# 1u_panel_v1_1.net
KiCad netlist of a schematic drawn in EAGLE
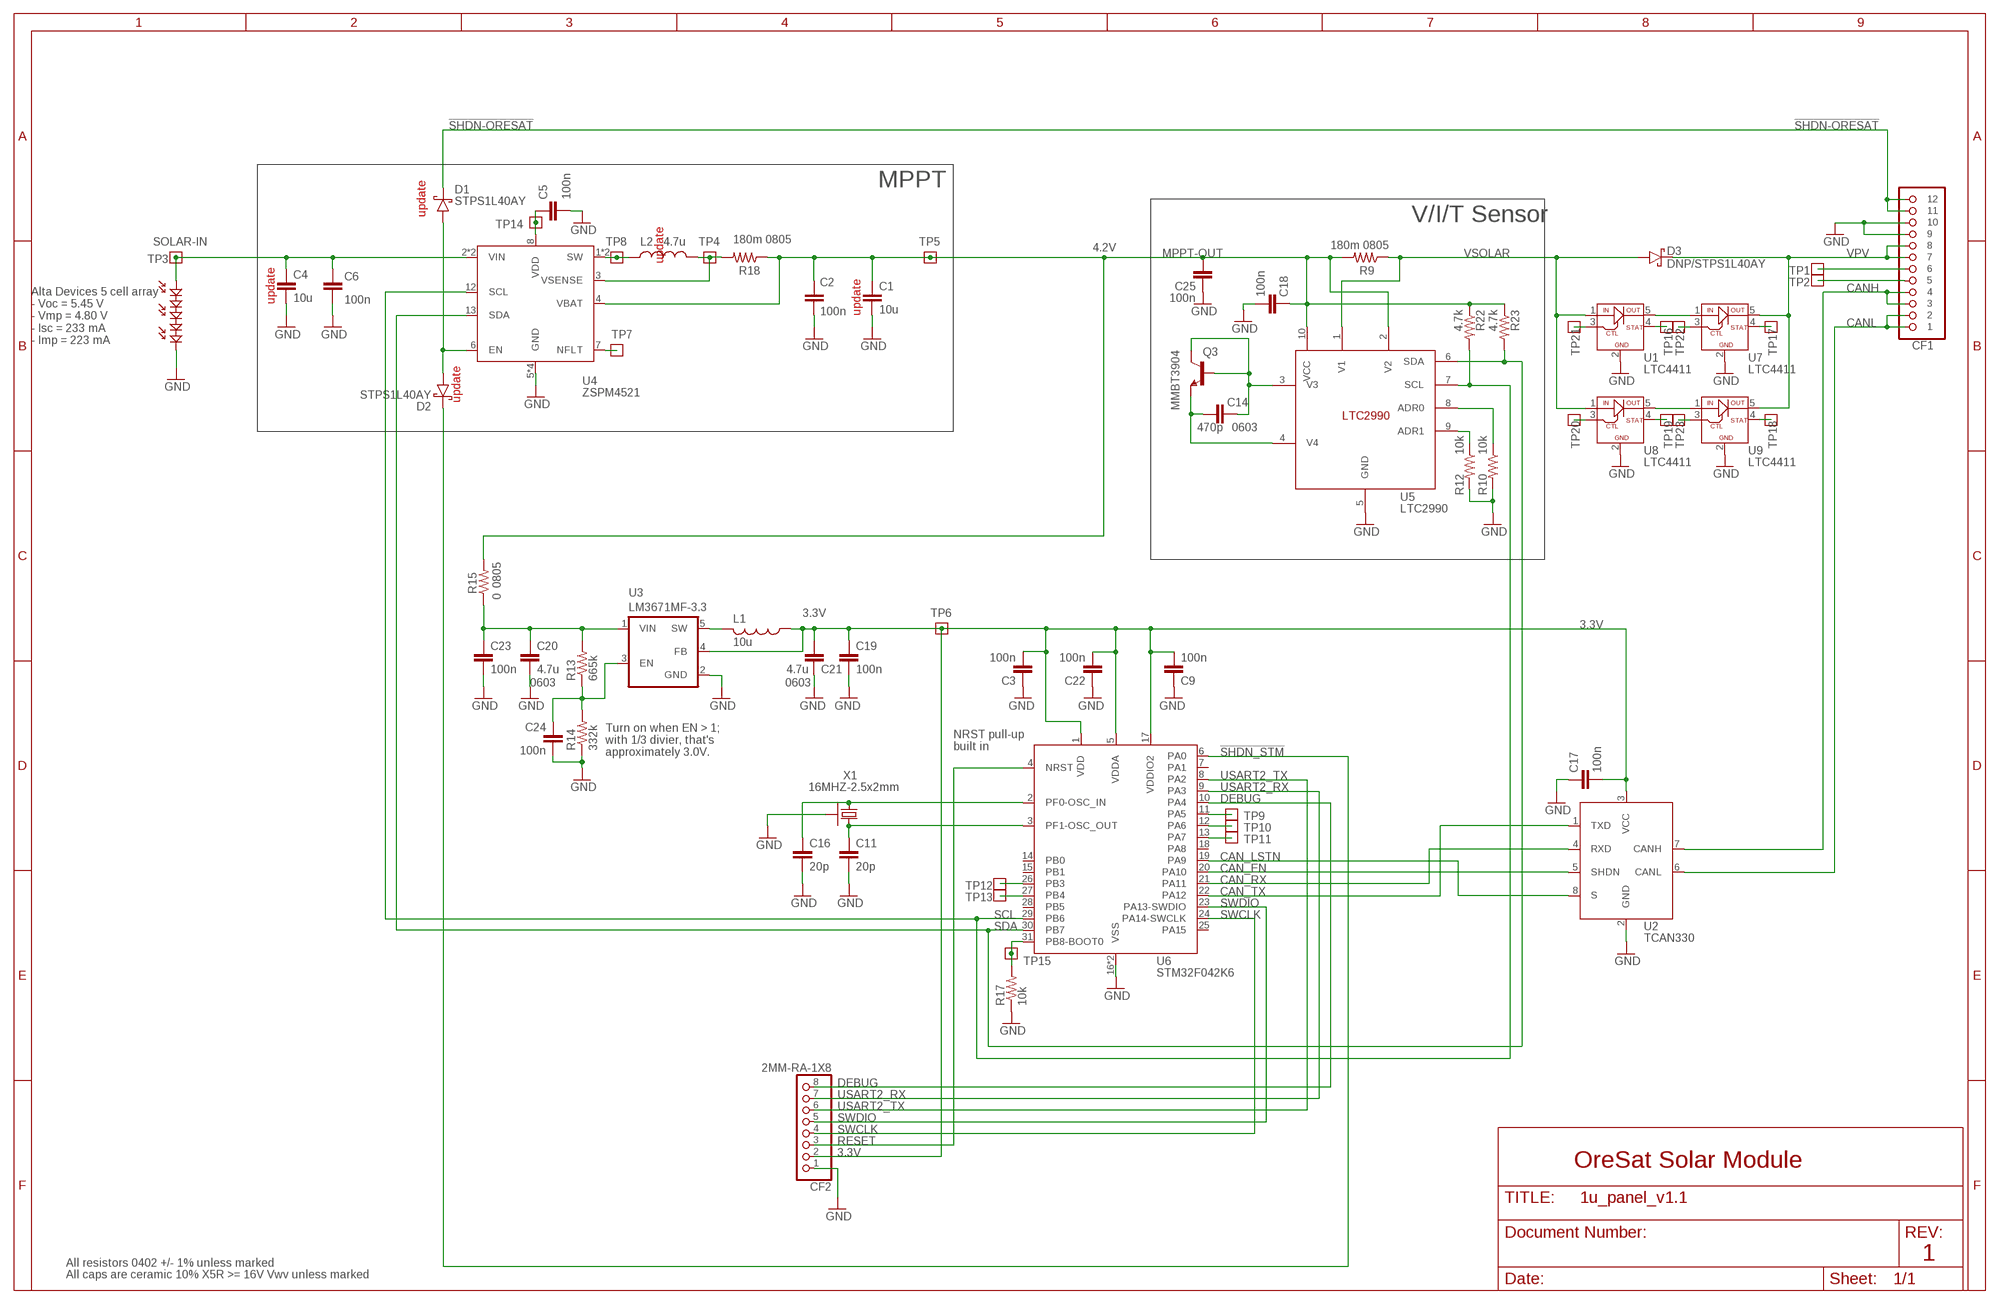
[diagram p0: schematic, sheet 1]

(export (version "E")
  (design (tool "Eeschema 10.0.6"))
  (components
    (comp (ref "C1")
      (value "10u")
      (footprint "eagle-import:1206-B")
      (fields (field (name "MFR") "Murata") (field (name "MPN") "GRM31CR71A226KE15L"))
      (libsource (lib "eagle-import") (part "C-EU1206-B"))
    )
    (comp (ref "C2")
      (value "100n")
      (footprint "eagle-import:.0402-B-NOSILK")
      (fields (field (name "MFR") "Samsung") (field (name "MPN") "CL05B104KO5NNNC"))
      (libsource (lib "eagle-import") (part "C-EU0402-B-NOSILK"))
    )
    (comp (ref "C3")
      (value "100n")
      (footprint "eagle-import:.0402-B-NOSILK")
      (fields (field (name "MFR") "Samsung") (field (name "MPN") "CL05B104KO5NNNC"))
      (libsource (lib "eagle-import") (part "C-EU0402-B-NOSILK"))
    )
    (comp (ref "C4")
      (value "10u")
      (footprint "eagle-import:1206-B")
      (fields (field (name "MFR") "Murata") (field (name "MPN") "GRM31CR71A226KE15L"))
      (libsource (lib "eagle-import") (part "C-EU1206-B"))
    )
    (comp (ref "C5")
      (value "100n")
      (footprint "eagle-import:.0402-B-NOSILK")
      (fields (field (name "MFR") "Samsung") (field (name "MPN") "CL05B104KO5NNNC"))
      (libsource (lib "eagle-import") (part "C-EU0402-B-NOSILK"))
    )
    (comp (ref "C6")
      (value "100n")
      (footprint "eagle-import:.0402-B-NOSILK")
      (fields (field (name "MFR") "Samsung") (field (name "MPN") "CL05B104KO5NNNC"))
      (libsource (lib "eagle-import") (part "C-EU0402-B-NOSILK"))
    )
    (comp (ref "C9")
      (value "100n")
      (footprint "eagle-import:.0402-B-NOSILK")
      (fields (field (name "MFR") "Samsung") (field (name "MPN") "CL05B104KO5NNNC"))
      (libsource (lib "eagle-import") (part "C-EU0402-B-NOSILK"))
    )
    (comp (ref "C11")
      (value "20p")
      (footprint "eagle-import:.0402-B-NOSILK")
      (fields (field (name "MFR") "Samsung") (field (name "MPN") "CL05C200JB51PNC"))
      (libsource (lib "eagle-import") (part "C-EU0402-B-NOSILK"))
    )
    (comp (ref "C14")
      (value "470p")
      (footprint "eagle-import:.0603-B-NOSILK")
      (fields (field (name "MFR") "Samsung") (field (name "MPN") "CL10A226MP8NUNE"))
      (libsource (lib "eagle-import") (part "C-EU0603-B-NOSILK"))
    )
    (comp (ref "C16")
      (value "20p")
      (footprint "eagle-import:.0402-B-NOSILK")
      (fields (field (name "MFR") "Samsung") (field (name "MPN") "CL05C200JB51PNC"))
      (libsource (lib "eagle-import") (part "C-EU0402-B-NOSILK"))
    )
    (comp (ref "C17")
      (value "100n")
      (footprint "eagle-import:.0402-B-NOSILK")
      (fields (field (name "MFR") "Samsung") (field (name "MPN") "CL05B104KO5NNNC"))
      (libsource (lib "eagle-import") (part "C-EU0402-B-NOSILK"))
    )
    (comp (ref "C18")
      (value "100n")
      (footprint "eagle-import:.0402-B-NOSILK")
      (fields (field (name "MFR") "Samsung") (field (name "MPN") "CL05B104KO5NNNC"))
      (libsource (lib "eagle-import") (part "C-EU0402-B-NOSILK"))
    )
    (comp (ref "C19")
      (value "100n")
      (footprint "eagle-import:.0402-B-NOSILK")
      (fields (field (name "MFR") "Samsung") (field (name "MPN") "CL05B104KO5NNNC"))
      (libsource (lib "eagle-import") (part "C-EU0402-B-NOSILK"))
    )
    (comp (ref "C20")
      (value "4.7u")
      (footprint "eagle-import:C0603")
      (fields (field (name "MFR") "Samsung") (field (name "MPN") "CL05B104KO5NNNC"))
      (libsource (lib "eagle-import") (part "C-EUC0603"))
    )
    (comp (ref "C21")
      (value "4.7u")
      (footprint "eagle-import:C0603")
      (fields (field (name "MFR") "Samsung") (field (name "MPN") "CL05B104KO5NNNC"))
      (libsource (lib "eagle-import") (part "C-EUC0603"))
    )
    (comp (ref "C22")
      (value "100n")
      (footprint "eagle-import:.0402-B-NOSILK")
      (fields (field (name "MFR") "Samsung") (field (name "MPN") "CL05B104KO5NNNC"))
      (libsource (lib "eagle-import") (part "C-EU0402-B-NOSILK"))
    )
    (comp (ref "C23")
      (value "100n")
      (footprint "eagle-import:.0402-B-NOSILK")
      (fields (field (name "MFR") "Samsung") (field (name "MPN") "CL05B104KO5NNNC"))
      (libsource (lib "eagle-import") (part "C-EU0402-B-NOSILK"))
    )
    (comp (ref "C24")
      (value "100n")
      (footprint "eagle-import:.0402-B-NOSILK")
      (fields (field (name "MFR") "Samsung") (field (name "MPN") "CL05B104KO5NNNC"))
      (libsource (lib "eagle-import") (part "C-EU0402-B-NOSILK"))
    )
    (comp (ref "C25")
      (value "100n")
      (footprint "eagle-import:.0402-B-NOSILK")
      (fields (field (name "MFR") "Samsung") (field (name "MPN") "CL05B104KO5NNNC"))
      (libsource (lib "eagle-import") (part "C-EU0402-B-NOSILK"))
    )
    (comp (ref "CF1")
      (value "15220122401000")
      (footprint "eagle-import:CON-1.27-F-HARTING-1522012X601XXX")
      (fields (field (name "MFR") "Harting"))
      (libsource (lib "eagle-import") (part "ORESAT-SOLARPANEL-12PIN"))
    )
    (comp (ref "CF2")
      (value "2MM-RA-1X8")
      (footprint "eagle-import:CF-2MM-RA-1X8-PRECIDIP-831")
      (fields (field (name "MFR") "PreciDip") (field (name "MPN") "831-87-050-40-001101"))
      (libsource (lib "eagle-import") (part "2MM-RA-1X8"))
    )
    (comp (ref "D1")
      (value "STPS1L40AY")
      (footprint "eagle-import:DO214AC")
      (fields (field (name "MFR") "ST"))
      (libsource (lib "eagle-import") (part "DIODE-DO214AC"))
    )
    (comp (ref "D2")
      (value "STPS1L40AY")
      (footprint "eagle-import:DO214AC")
      (fields (field (name "MFR") "ST"))
      (libsource (lib "eagle-import") (part "DIODE-DO214AC"))
    )
    (comp (ref "D3")
      (value "DNP/STPS1L40AY")
      (footprint "eagle-import:DO214AC")
      (fields (field (name "MFR") "ST") (field (name "MPN") "STPS1L40AY"))
      (libsource (lib "eagle-import") (part "DIODE-DO214AC"))
    )
    (comp (ref "L1")
      (value "10u")
      (footprint "eagle-import:L2012C")
      (fields (field (name "MFR") "Taiyo Yuden") (field (name "MPN") "CB2012T100KR"))
      (libsource (lib "eagle-import") (part "L-USL2012C"))
    )
    (comp (ref "L2")
      (value "4.7u")
      (footprint "eagle-import:VISHAY-DALE-IFSR-1515AHER")
      (fields (field (name "MFR") "Vishay Dale") (field (name "MPN") "IFSC1515AHER220M01"))
      (libsource (lib "eagle-import") (part "L-VISHAY-DALE-IFSC-1515AHER"))
    )
    (comp (ref "PV1")
      (value "ALTA-5-CELL-ARRAYALTA-FIVE-CELL-SLOT")
      (footprint "eagle-import:ALTA-FIVE-CELL-THROUGH-SLOT")
      (libsource (lib "eagle-import") (part "ALTA-5-CELL-ARRAYALTA-FIVE-CELL-SLOT"))
    )
    (comp (ref "Q3")
      (value "MMBT3904")
      (footprint "eagle-import:SOT23HOLE")
      (fields (field (name "MFR") "Fairchild/ON Semiconductor"))
      (libsource (lib "eagle-import") (part "DIODE-INC-NPNSOT23HOLE"))
    )
    (comp (ref "R9")
      (value "180m 0805")
      (footprint "eagle-import:.0805-B-NOSILK")
      (fields (field (name "MFR") "Vishay Dale") (field (name "MPN") "RCWE0805R180FKEA"))
      (libsource (lib "eagle-import") (part "R-US_0805-B-NOSILK"))
    )
    (comp (ref "R10")
      (value "10k")
      (footprint "eagle-import:.0402-B-NOSILK")
      (fields (field (name "MFR") "Rohm Semiconductor") (field (name "MPN") "MCR01MZPF1002"))
      (libsource (lib "eagle-import") (part "R-US_0402-B-NOSILK"))
    )
    (comp (ref "R12")
      (value "10k")
      (footprint "eagle-import:.0402-B-NOSILK")
      (fields (field (name "MFR") "Rohm Semiconductor") (field (name "MPN") "MCR01MZPF1002"))
      (libsource (lib "eagle-import") (part "R-US_0402-B-NOSILK"))
    )
    (comp (ref "R13")
      (value "665k")
      (footprint "eagle-import:.0402-B-NOSILK")
      (fields (field (name "MFR") "Samsung") (field (name "MPN") "RC1005F6653CS"))
      (libsource (lib "eagle-import") (part "R-US_0402-B-NOSILK"))
    )
    (comp (ref "R14")
      (value "332k")
      (footprint "eagle-import:.0402-B-NOSILK")
      (fields (field (name "MFR") "Samsung") (field (name "MPN") "RC1005F3323CS"))
      (libsource (lib "eagle-import") (part "R-US_0402-B-NOSILK"))
    )
    (comp (ref "R15")
      (value "0")
      (footprint "eagle-import:.0805-B-NOSILK")
      (fields (field (name "MFR") "Rohm") (field (name "MPN") "MCR10EZPJ000"))
      (libsource (lib "eagle-import") (part "R-US_0805-B-NOSILK"))
    )
    (comp (ref "R17")
      (value "10k")
      (footprint "eagle-import:.0402-B-NOSILK")
      (fields (field (name "MFR") "Samsung") (field (name "MPN") "RC1005F6653CS"))
      (libsource (lib "eagle-import") (part "R-US_0402-B-NOSILK"))
    )
    (comp (ref "R18")
      (value "180m 0805")
      (footprint "eagle-import:.0805-B-NOSILK")
      (fields (field (name "MFR") "Vishay Dale") (field (name "MPN") "RCWE0805R180FKEA"))
      (libsource (lib "eagle-import") (part "R-US_0805-B-NOSILK"))
    )
    (comp (ref "R22")
      (value "4.7k")
      (footprint "eagle-import:.0402-B-NOSILK")
      (fields (field (name "MFR") "Rohm Semiconductor") (field (name "MPN") "TRR01MZPF4701"))
      (libsource (lib "eagle-import") (part "R-US_0402-B-NOSILK"))
    )
    (comp (ref "R23")
      (value "4.7k")
      (footprint "eagle-import:.0402-B-NOSILK")
      (fields (field (name "MFR") "Rohm Semiconductor") (field (name "MPN") "TRR01MZPF4701"))
      (libsource (lib "eagle-import") (part "R-US_0402-B-NOSILK"))
    )
    (comp (ref "TP1")
      (value "TEST-POINT")
      (footprint "eagle-import:2MM-TEST-POINT")
      (libsource (lib "eagle-import") (part "TEST-POINT"))
    )
    (comp (ref "TP2")
      (value "TEST-POINT")
      (footprint "eagle-import:2MM-TEST-POINT")
      (libsource (lib "eagle-import") (part "TEST-POINT"))
    )
    (comp (ref "TP3")
      (value "TEST-POINT")
      (footprint "eagle-import:2MM-TEST-POINT")
      (libsource (lib "eagle-import") (part "TEST-POINT"))
    )
    (comp (ref "TP4")
      (value "TEST-POINT")
      (footprint "eagle-import:2MM-TEST-POINT")
      (libsource (lib "eagle-import") (part "TEST-POINT"))
    )
    (comp (ref "TP5")
      (value "TEST-POINT")
      (footprint "eagle-import:2MM-TEST-POINT")
      (libsource (lib "eagle-import") (part "TEST-POINT"))
    )
    (comp (ref "TP6")
      (value "TEST-POINT")
      (footprint "eagle-import:2MM-TEST-POINT")
      (libsource (lib "eagle-import") (part "TEST-POINT"))
    )
    (comp (ref "TP7")
      (value "TEST-POINT")
      (footprint "eagle-import:2MM-TEST-POINT")
      (libsource (lib "eagle-import") (part "TEST-POINT"))
    )
    (comp (ref "TP8")
      (value "TEST-POINT")
      (footprint "eagle-import:2MM-TEST-POINT")
      (libsource (lib "eagle-import") (part "TEST-POINT"))
    )
    (comp (ref "TP9")
      (value "TEST-POINT")
      (footprint "eagle-import:2MM-TEST-POINT")
      (libsource (lib "eagle-import") (part "TEST-POINT"))
    )
    (comp (ref "TP10")
      (value "TEST-POINT")
      (footprint "eagle-import:2MM-TEST-POINT")
      (libsource (lib "eagle-import") (part "TEST-POINT"))
    )
    (comp (ref "TP11")
      (value "TEST-POINT")
      (footprint "eagle-import:2MM-TEST-POINT")
      (libsource (lib "eagle-import") (part "TEST-POINT"))
    )
    (comp (ref "TP12")
      (value "TEST-POINT")
      (footprint "eagle-import:2MM-TEST-POINT")
      (libsource (lib "eagle-import") (part "TEST-POINT"))
    )
    (comp (ref "TP13")
      (value "TEST-POINT")
      (footprint "eagle-import:2MM-TEST-POINT")
      (libsource (lib "eagle-import") (part "TEST-POINT"))
    )
    (comp (ref "TP14")
      (value "TEST-POINT")
      (footprint "eagle-import:2MM-TEST-POINT")
      (libsource (lib "eagle-import") (part "TEST-POINT"))
    )
    (comp (ref "TP15")
      (value "TEST-POINT")
      (footprint "eagle-import:2MM-TEST-POINT")
      (libsource (lib "eagle-import") (part "TEST-POINT"))
    )
    (comp (ref "TP16")
      (value "TEST-POINT")
      (footprint "eagle-import:2MM-TEST-POINT")
      (libsource (lib "eagle-import") (part "TEST-POINT"))
    )
    (comp (ref "TP17")
      (value "TEST-POINT")
      (footprint "eagle-import:2MM-TEST-POINT")
      (libsource (lib "eagle-import") (part "TEST-POINT"))
    )
    (comp (ref "TP18")
      (value "TEST-POINT")
      (footprint "eagle-import:2MM-TEST-POINT")
      (libsource (lib "eagle-import") (part "TEST-POINT"))
    )
    (comp (ref "TP19")
      (value "TEST-POINT")
      (footprint "eagle-import:2MM-TEST-POINT")
      (libsource (lib "eagle-import") (part "TEST-POINT"))
    )
    (comp (ref "TP20")
      (value "TEST-POINT")
      (footprint "eagle-import:2MM-TEST-POINT")
      (libsource (lib "eagle-import") (part "TEST-POINT"))
    )
    (comp (ref "TP21")
      (value "TEST-POINT")
      (footprint "eagle-import:2MM-TEST-POINT")
      (libsource (lib "eagle-import") (part "TEST-POINT"))
    )
    (comp (ref "TP22")
      (value "TEST-POINT")
      (footprint "eagle-import:2MM-TEST-POINT")
      (libsource (lib "eagle-import") (part "TEST-POINT"))
    )
    (comp (ref "TP23")
      (value "TEST-POINT")
      (footprint "eagle-import:2MM-TEST-POINT")
      (libsource (lib "eagle-import") (part "TEST-POINT"))
    )
    (comp (ref "U1")
      (value "LTC4411")
      (footprint "eagle-import:SOT23-5-B")
      (libsource (lib "eagle-import") (part "LTC4411"))
    )
    (comp (ref "U2")
      (value "TCAN330")
      (footprint "eagle-import:SOT23-8_TI-DCN")
      (fields (field (name "MFR") "Texas Instruments") (field (name "MPN") "TCAN330GDCNT"))
      (libsource (lib "eagle-import") (part "TCAN330"))
    )
    (comp (ref "U3")
      (value "LM3671MF-3.3")
      (footprint "eagle-import:SOT23-5")
      (fields (field (name "MFR") "TI") (field (name "MPN") "LM3671MF-3.3/NOPB"))
      (libsource (lib "eagle-import") (part "LM3761"))
    )
    (comp (ref "U4")
      (value "ZSPM4521")
      (footprint "eagle-import:QFN-16(4X4)")
      (libsource (lib "eagle-import") (part "ZSPM4521"))
    )
    (comp (ref "U5")
      (value "LTC2990")
      (footprint "eagle-import:MSOP10")
      (fields (field (name "MFR") "Linear Technology") (field (name "MPN") "LTC2990CMS#PBF"))
      (libsource (lib "eagle-import") (part "LTC2990"))
    )
    (comp (ref "U6")
      (value "STM32F042K6")
      (footprint "eagle-import:QFP32-7X7")
      (fields (field (name "MFR") "STMicroelectronics") (field (name "MPN") "STM32F042K6T7"))
      (libsource (lib "eagle-import") (part "STM32F042K6"))
    )
    (comp (ref "U7")
      (value "LTC4411")
      (footprint "eagle-import:SOT23-5-B")
      (libsource (lib "eagle-import") (part "LTC4411"))
    )
    (comp (ref "U8")
      (value "LTC4411")
      (footprint "eagle-import:SOT23-5-B")
      (libsource (lib "eagle-import") (part "LTC4411"))
    )
    (comp (ref "U9")
      (value "LTC4411")
      (footprint "eagle-import:SOT23-5-B")
      (libsource (lib "eagle-import") (part "LTC4411"))
    )
    (comp (ref "X1")
      (value "16MHZ-2.5x2mm")
      (footprint "eagle-import:CRYSTAL_2.5X2")
      (fields (field (name "MFR") "ECS Inc.") (field (name "MPN") "ECS-160-10-36Q-ES-TR"))
      (libsource (lib "eagle-import") (part "CRYSTAL-WITH-GND"))
    )
  )
  (nets
    (net (code "1") (name "/3.3V") (class "Default")
      (node (ref "C17") (pin "2") (pinfunction "2_2") (pintype "passive"))
      (node (ref "C19") (pin "1") (pinfunction "1_1") (pintype "passive"))
      (node (ref "C21") (pin "1") (pinfunction "1_1") (pintype "passive"))
      (node (ref "C22") (pin "2") (pinfunction "2_2") (pintype "passive"))
      (node (ref "C3") (pin "2") (pinfunction "2_2") (pintype "passive"))
      (node (ref "C9") (pin "2") (pinfunction "2_2") (pintype "passive"))
      (node (ref "CF2") (pin "2") (pinfunction "2_2") (pintype "passive"))
      (node (ref "L1") (pin "1") (pinfunction "1_1") (pintype "passive"))
      (node (ref "TP6") (pin "1") (pinfunction "1_1") (pintype "passive"))
      (node (ref "U2") (pin "3") (pinfunction "VCC_3") (pintype "power_in"))
      (node (ref "U3") (pin "4") (pinfunction "FB_4") (pintype "input"))
      (node (ref "U6") (pin "1") (pinfunction "VDD_1") (pintype "power_in"))
      (node (ref "U6") (pin "17") (pinfunction "VDDIO2_17") (pintype "power_in"))
      (node (ref "U6") (pin "5") (pinfunction "VDDA_5") (pintype "power_in"))
    )
    (net (code "2") (name "/CANH") (class "Default")
      (node (ref "CF1") (pin "3") (pinfunction "3_3") (pintype "passive"))
      (node (ref "CF1") (pin "4") (pinfunction "4_4") (pintype "passive"))
      (node (ref "U2") (pin "7") (pinfunction "CANH_7") (pintype "bidirectional"))
    )
    (net (code "3") (name "/CANL") (class "Default")
      (node (ref "CF1") (pin "1") (pinfunction "1_1") (pintype "passive"))
      (node (ref "CF1") (pin "2") (pinfunction "2_2") (pintype "passive"))
      (node (ref "U2") (pin "6") (pinfunction "CANL_6") (pintype "bidirectional"))
    )
    (net (code "4") (name "/CAN_EN") (class "Default")
      (node (ref "U2") (pin "5") (pinfunction "SHDN_5") (pintype "input"))
      (node (ref "U6") (pin "20") (pinfunction "PA10_20") (pintype "bidirectional"))
    )
    (net (code "5") (name "/CAN_LSTN") (class "Default")
      (node (ref "U2") (pin "8") (pinfunction "S_8") (pintype "input"))
      (node (ref "U6") (pin "19") (pinfunction "PA9_19") (pintype "bidirectional"))
    )
    (net (code "6") (name "/CAN_RX") (class "Default")
      (node (ref "U2") (pin "4") (pinfunction "RXD_4") (pintype "output"))
      (node (ref "U6") (pin "21") (pinfunction "PA11_21") (pintype "bidirectional"))
    )
    (net (code "7") (name "/CAN_TX") (class "Default")
      (node (ref "U2") (pin "1") (pinfunction "TXD_1") (pintype "input"))
      (node (ref "U6") (pin "22") (pinfunction "PA12_22") (pintype "bidirectional"))
    )
    (net (code "8") (name "/DEBUG") (class "Default")
      (node (ref "CF2") (pin "8") (pinfunction "8_8") (pintype "passive"))
      (node (ref "U6") (pin "10") (pinfunction "PA4_10") (pintype "bidirectional"))
    )
    (net (code "9") (name "/MPPT-OUT") (class "Default")
      (node (ref "C1") (pin "1") (pinfunction "1_1") (pintype "passive"))
      (node (ref "C18") (pin "1") (pinfunction "1_1") (pintype "passive"))
      (node (ref "C2") (pin "1") (pinfunction "1_1") (pintype "passive"))
      (node (ref "C25") (pin "2") (pinfunction "2_2") (pintype "passive"))
      (node (ref "R15") (pin "2") (pinfunction "2_2") (pintype "passive"))
      (node (ref "R18") (pin "1") (pinfunction "1_1") (pintype "passive"))
      (node (ref "R22") (pin "1") (pinfunction "1_1") (pintype "passive"))
      (node (ref "R23") (pin "1") (pinfunction "1_1") (pintype "passive"))
      (node (ref "R9") (pin "2") (pinfunction "2_2") (pintype "passive"))
      (node (ref "TP5") (pin "1") (pinfunction "1_1") (pintype "passive"))
      (node (ref "U4") (pin "4") (pinfunction "VBAT_4") (pintype "input"))
      (node (ref "U5") (pin "10") (pinfunction "VCC_10") (pintype "bidirectional"))
      (node (ref "U5") (pin "2") (pinfunction "V2_2") (pintype "bidirectional"))
    )
    (net (code "10") (name "/RESET") (class "Default")
      (node (ref "CF2") (pin "3") (pinfunction "3_3") (pintype "passive"))
      (node (ref "U6") (pin "4") (pinfunction "NRST_4") (pintype "bidirectional"))
    )
    (net (code "11") (name "/SCL") (class "Default")
      (node (ref "R22") (pin "2") (pinfunction "2_2") (pintype "passive"))
      (node (ref "U4") (pin "12") (pinfunction "SCL_12") (pintype "input"))
      (node (ref "U5") (pin "7") (pinfunction "SCL_7") (pintype "bidirectional"))
      (node (ref "U6") (pin "29") (pinfunction "PB6_29") (pintype "bidirectional"))
    )
    (net (code "12") (name "/SDA") (class "Default")
      (node (ref "R23") (pin "2") (pinfunction "2_2") (pintype "passive"))
      (node (ref "U4") (pin "13") (pinfunction "SDA_13") (pintype "bidirectional"))
      (node (ref "U5") (pin "6") (pinfunction "SDA_6") (pintype "bidirectional"))
      (node (ref "U6") (pin "30") (pinfunction "PB7_30") (pintype "bidirectional"))
    )
    (net (code "13") (name "/SOLAR-IN") (class "Default")
      (node (ref "C4") (pin "1") (pinfunction "1_1") (pintype "passive"))
      (node (ref "C6") (pin "1") (pinfunction "1_1") (pintype "passive"))
      (node (ref "PV1") (pin "POS1") (pinfunction "POS_POS1") (pintype "power_in"))
      (node (ref "PV1") (pin "POS2") (pinfunction "POS_POS2") (pintype "power_in"))
      (node (ref "TP3") (pin "1") (pinfunction "1_1") (pintype "passive"))
      (node (ref "U4") (pin "11") (pinfunction "VIN_11") (pintype "power_in"))
      (node (ref "U4") (pin "2") (pinfunction "VIN_2") (pintype "power_in"))
    )
    (net (code "14") (name "/SWCLK") (class "Default")
      (node (ref "CF2") (pin "4") (pinfunction "4_4") (pintype "passive"))
      (node (ref "U6") (pin "24") (pinfunction "PA14-SWCLK_24") (pintype "bidirectional"))
    )
    (net (code "15") (name "/SWDIO") (class "Default")
      (node (ref "CF2") (pin "5") (pinfunction "5_5") (pintype "passive"))
      (node (ref "U6") (pin "23") (pinfunction "PA13-SWDIO_23") (pintype "bidirectional"))
    )
    (net (code "16") (name "/USART2_RX") (class "Default")
      (node (ref "CF2") (pin "7") (pinfunction "7_7") (pintype "passive"))
      (node (ref "U6") (pin "9") (pinfunction "PA3_9") (pintype "bidirectional"))
    )
    (net (code "17") (name "/USART2_TX") (class "Default")
      (node (ref "CF2") (pin "6") (pinfunction "6_6") (pintype "passive"))
      (node (ref "U6") (pin "8") (pinfunction "PA2_8") (pintype "bidirectional"))
    )
    (net (code "18") (name "/VPV") (class "Default")
      (node (ref "CF1") (pin "7") (pinfunction "7_7") (pintype "passive"))
      (node (ref "CF1") (pin "8") (pinfunction "8_8") (pintype "passive"))
      (node (ref "D3") (pin "C") (pinfunction "C_C") (pintype "passive"))
      (node (ref "U7") (pin "5") (pinfunction "OUT_5") (pintype "output"))
      (node (ref "U9") (pin "5") (pinfunction "OUT_5") (pintype "output"))
    )
    (net (code "19") (name "/VSOLAR") (class "Default")
      (node (ref "D3") (pin "A") (pinfunction "A_A") (pintype "passive"))
      (node (ref "R9") (pin "1") (pinfunction "1_1") (pintype "passive"))
      (node (ref "U1") (pin "1") (pinfunction "IN_1") (pintype "input"))
      (node (ref "U5") (pin "1") (pinfunction "V1_1") (pintype "bidirectional"))
      (node (ref "U8") (pin "1") (pinfunction "IN_1") (pintype "input"))
    )
    (net (code "20") (name "/~{SHDN-ORESAT}") (class "Default")
      (node (ref "CF1") (pin "11") (pinfunction "11_11") (pintype "passive"))
      (node (ref "CF1") (pin "12") (pinfunction "12_12") (pintype "passive"))
      (node (ref "D1") (pin "C") (pinfunction "C_C") (pintype "passive"))
    )
    (net (code "21") (name "/~{SHDN_STM}") (class "Default")
      (node (ref "D2") (pin "C") (pinfunction "C_C") (pintype "passive"))
      (node (ref "U6") (pin "6") (pinfunction "PA0_6") (pintype "bidirectional"))
    )
    (net (code "22") (name "GND") (class "Default")
      (node (ref "C1") (pin "2") (pinfunction "2_2") (pintype "passive"))
      (node (ref "C11") (pin "2") (pinfunction "2_2") (pintype "passive"))
      (node (ref "C16") (pin "2") (pinfunction "2_2") (pintype "passive"))
      (node (ref "C17") (pin "1") (pinfunction "1_1") (pintype "passive"))
      (node (ref "C18") (pin "2") (pinfunction "2_2") (pintype "passive"))
      (node (ref "C19") (pin "2") (pinfunction "2_2") (pintype "passive"))
      (node (ref "C2") (pin "2") (pinfunction "2_2") (pintype "passive"))
      (node (ref "C20") (pin "2") (pinfunction "2_2") (pintype "passive"))
      (node (ref "C21") (pin "2") (pinfunction "2_2") (pintype "passive"))
      (node (ref "C22") (pin "1") (pinfunction "1_1") (pintype "passive"))
      (node (ref "C23") (pin "2") (pinfunction "2_2") (pintype "passive"))
      (node (ref "C24") (pin "2") (pinfunction "2_2") (pintype "passive"))
      (node (ref "C25") (pin "1") (pinfunction "1_1") (pintype "passive"))
      (node (ref "C3") (pin "1") (pinfunction "1_1") (pintype "passive"))
      (node (ref "C4") (pin "2") (pinfunction "2_2") (pintype "passive"))
      (node (ref "C5") (pin "2") (pinfunction "2_2") (pintype "passive"))
      (node (ref "C6") (pin "2") (pinfunction "2_2") (pintype "passive"))
      (node (ref "C9") (pin "1") (pinfunction "1_1") (pintype "passive"))
      (node (ref "CF1") (pin "10") (pinfunction "10_10") (pintype "passive"))
      (node (ref "CF1") (pin "9") (pinfunction "9_9") (pintype "passive"))
      (node (ref "CF2") (pin "1") (pinfunction "1_1") (pintype "passive"))
      (node (ref "PV1") (pin "NEG1") (pinfunction "NEG_NEG1") (pintype "power_in"))
      (node (ref "PV1") (pin "NEG2") (pinfunction "NEG_NEG2") (pintype "power_in"))
      (node (ref "R10") (pin "2") (pinfunction "2_2") (pintype "passive"))
      (node (ref "R12") (pin "2") (pinfunction "2_2") (pintype "passive"))
      (node (ref "R14") (pin "1") (pinfunction "1_1") (pintype "passive"))
      (node (ref "R17") (pin "1") (pinfunction "1_1") (pintype "passive"))
      (node (ref "U1") (pin "2") (pinfunction "GND_2") (pintype "power_in"))
      (node (ref "U2") (pin "2") (pinfunction "GND_2") (pintype "power_in"))
      (node (ref "U3") (pin "2") (pinfunction "GND_2") (pintype "bidirectional"))
      (node (ref "U4") (pin "15") (pinfunction "GND_15") (pintype "bidirectional"))
      (node (ref "U4") (pin "16") (pinfunction "GND_16") (pintype "bidirectional"))
      (node (ref "U4") (pin "5") (pinfunction "GND_5") (pintype "bidirectional"))
      (node (ref "U4") (pin "PAD") (pinfunction "GND_PAD") (pintype "bidirectional"))
      (node (ref "U5") (pin "5") (pinfunction "GND_5") (pintype "bidirectional"))
      (node (ref "U6") (pin "16") (pinfunction "VSS_16") (pintype "power_in"))
      (node (ref "U6") (pin "32") (pinfunction "VSS_32") (pintype "power_in"))
      (node (ref "U7") (pin "2") (pinfunction "GND_2") (pintype "power_in"))
      (node (ref "U8") (pin "2") (pinfunction "GND_2") (pintype "power_in"))
      (node (ref "U9") (pin "2") (pinfunction "GND_2") (pintype "power_in"))
      (node (ref "X1") (pin "2") (pinfunction "SHIELD_2") (pintype "power_in"))
      (node (ref "X1") (pin "4") (pinfunction "SHIELD_4") (pintype "power_in"))
    )
    (net (code "23") (name "Net-(CF1-Pad5)") (class "Default")
      (node (ref "CF1") (pin "5") (pinfunction "5_5") (pintype "passive"))
      (node (ref "TP2") (pin "1") (pinfunction "1_1") (pintype "passive"))
    )
    (net (code "24") (name "Net-(CF1-Pad6)") (class "Default")
      (node (ref "CF1") (pin "6") (pinfunction "6_6") (pintype "passive"))
      (node (ref "TP1") (pin "1") (pinfunction "1_1") (pintype "passive"))
    )
    (net (code "25") (name "Net-(L2-Pad2)") (class "Default")
      (node (ref "L2") (pin "2") (pinfunction "2_2") (pintype "passive"))
      (node (ref "TP8") (pin "1") (pinfunction "1_1") (pintype "passive"))
      (node (ref "U4") (pin "1") (pinfunction "SW_1") (pintype "power_in"))
      (node (ref "U4") (pin "14") (pinfunction "SW_14") (pintype "power_in"))
    )
    (net (code "26") (name "Net-(Q3-B)") (class "Default")
      (node (ref "C14") (pin "2") (pinfunction "2_2") (pintype "passive"))
      (node (ref "Q3") (pin "1") (pinfunction "B_1") (pintype "passive"))
      (node (ref "Q3") (pin "3") (pinfunction "C_3") (pintype "passive"))
      (node (ref "U5") (pin "3") (pinfunction "V3_3") (pintype "bidirectional"))
    )
    (net (code "27") (name "Net-(Q3-E)") (class "Default")
      (node (ref "C14") (pin "1") (pinfunction "1_1") (pintype "passive"))
      (node (ref "Q3") (pin "2") (pinfunction "E_2") (pintype "passive"))
      (node (ref "U5") (pin "4") (pinfunction "V4_4") (pintype "bidirectional"))
    )
    (net (code "28") (name "Net-(U1-CTL)") (class "Default")
      (node (ref "TP21") (pin "1") (pinfunction "1_1") (pintype "passive"))
      (node (ref "U1") (pin "3") (pinfunction "CTL_3") (pintype "input"))
    )
    (net (code "29") (name "Net-(U1-OUT)") (class "Default")
      (node (ref "U1") (pin "5") (pinfunction "OUT_5") (pintype "output"))
      (node (ref "U7") (pin "1") (pinfunction "IN_1") (pintype "input"))
    )
    (net (code "30") (name "Net-(U1-STAT)") (class "Default")
      (node (ref "TP16") (pin "1") (pinfunction "1_1") (pintype "passive"))
      (node (ref "U1") (pin "4") (pinfunction "STAT_4") (pintype "output"))
    )
    (net (code "31") (name "Net-(U3-EN)") (class "Default")
      (node (ref "C24") (pin "1") (pinfunction "1_1") (pintype "passive"))
      (node (ref "R13") (pin "1") (pinfunction "1_1") (pintype "passive"))
      (node (ref "R14") (pin "2") (pinfunction "2_2") (pintype "passive"))
      (node (ref "U3") (pin "3") (pinfunction "EN_3") (pintype "input"))
    )
    (net (code "32") (name "Net-(U3-SW)") (class "Default")
      (node (ref "L1") (pin "2") (pinfunction "2_2") (pintype "passive"))
      (node (ref "U3") (pin "5") (pinfunction "SW_5") (pintype "bidirectional"))
    )
    (net (code "33") (name "Net-(U3-VIN)") (class "Default")
      (node (ref "C20") (pin "1") (pinfunction "1_1") (pintype "passive"))
      (node (ref "C23") (pin "1") (pinfunction "1_1") (pintype "passive"))
      (node (ref "R13") (pin "2") (pinfunction "2_2") (pintype "passive"))
      (node (ref "R15") (pin "1") (pinfunction "1_1") (pintype "passive"))
      (node (ref "U3") (pin "1") (pinfunction "VIN_1") (pintype "bidirectional"))
    )
    (net (code "34") (name "Net-(U4-EN)") (class "Default")
      (node (ref "D1") (pin "A") (pinfunction "A_A") (pintype "passive"))
      (node (ref "D2") (pin "A") (pinfunction "A_A") (pintype "passive"))
      (node (ref "U4") (pin "6") (pinfunction "EN_6") (pintype "input"))
    )
    (net (code "35") (name "Net-(U4-NFLT)") (class "Default")
      (node (ref "TP7") (pin "1") (pinfunction "1_1") (pintype "passive"))
      (node (ref "U4") (pin "7") (pinfunction "NFLT_7") (pintype "open_collector"))
    )
    (net (code "36") (name "Net-(U4-VDD)") (class "Default")
      (node (ref "C5") (pin "1") (pinfunction "1_1") (pintype "passive"))
      (node (ref "TP14") (pin "1") (pinfunction "1_1") (pintype "passive"))
      (node (ref "U4") (pin "8") (pinfunction "VDD_8") (pintype "power_in"))
    )
    (net (code "37") (name "Net-(U4-VSENSE)") (class "Default")
      (node (ref "L2") (pin "1") (pinfunction "1_1") (pintype "passive"))
      (node (ref "R18") (pin "2") (pinfunction "2_2") (pintype "passive"))
      (node (ref "TP4") (pin "1") (pinfunction "1_1") (pintype "passive"))
      (node (ref "U4") (pin "3") (pinfunction "VSENSE_3") (pintype "input"))
    )
    (net (code "38") (name "Net-(U5-ADR0)") (class "Default")
      (node (ref "R10") (pin "1") (pinfunction "1_1") (pintype "passive"))
      (node (ref "U5") (pin "8") (pinfunction "ADR0_8") (pintype "bidirectional"))
    )
    (net (code "39") (name "Net-(U5-ADR1)") (class "Default")
      (node (ref "R12") (pin "1") (pinfunction "1_1") (pintype "passive"))
      (node (ref "U5") (pin "9") (pinfunction "ADR1_9") (pintype "bidirectional"))
    )
    (net (code "40") (name "Net-(U6-PA5)") (class "Default")
      (node (ref "TP9") (pin "1") (pinfunction "1_1") (pintype "passive"))
      (node (ref "U6") (pin "11") (pinfunction "PA5_11") (pintype "bidirectional"))
    )
    (net (code "41") (name "Net-(U6-PA6)") (class "Default")
      (node (ref "TP10") (pin "1") (pinfunction "1_1") (pintype "passive"))
      (node (ref "U6") (pin "12") (pinfunction "PA6_12") (pintype "bidirectional"))
    )
    (net (code "42") (name "Net-(U6-PA7)") (class "Default")
      (node (ref "TP11") (pin "1") (pinfunction "1_1") (pintype "passive"))
      (node (ref "U6") (pin "13") (pinfunction "PA7_13") (pintype "bidirectional"))
    )
    (net (code "43") (name "Net-(U6-PB3)") (class "Default")
      (node (ref "TP12") (pin "1") (pinfunction "1_1") (pintype "passive"))
      (node (ref "U6") (pin "26") (pinfunction "PB3_26") (pintype "bidirectional"))
    )
    (net (code "44") (name "Net-(U6-PB4)") (class "Default")
      (node (ref "TP13") (pin "1") (pinfunction "1_1") (pintype "passive"))
      (node (ref "U6") (pin "27") (pinfunction "PB4_27") (pintype "bidirectional"))
    )
    (net (code "45") (name "Net-(U6-PB8-BOOT0)") (class "Default")
      (node (ref "R17") (pin "2") (pinfunction "2_2") (pintype "passive"))
      (node (ref "TP15") (pin "1") (pinfunction "1_1") (pintype "passive"))
      (node (ref "U6") (pin "31") (pinfunction "PB8-BOOT0_31") (pintype "bidirectional"))
    )
    (net (code "46") (name "Net-(U6-PF0-OSC_IN)") (class "Default")
      (node (ref "C16") (pin "1") (pinfunction "1_1") (pintype "passive"))
      (node (ref "U6") (pin "2") (pinfunction "PF0-OSC_IN_2") (pintype "bidirectional"))
      (node (ref "X1") (pin "1") (pinfunction "1_1") (pintype "passive"))
    )
    (net (code "47") (name "Net-(U6-PF1-OSC_OUT)") (class "Default")
      (node (ref "C11") (pin "1") (pinfunction "1_1") (pintype "passive"))
      (node (ref "U6") (pin "3") (pinfunction "PF1-OSC_OUT_3") (pintype "bidirectional"))
      (node (ref "X1") (pin "3") (pinfunction "2_3") (pintype "passive"))
    )
    (net (code "48") (name "Net-(U7-CTL)") (class "Default")
      (node (ref "TP22") (pin "1") (pinfunction "1_1") (pintype "passive"))
      (node (ref "U7") (pin "3") (pinfunction "CTL_3") (pintype "input"))
    )
    (net (code "49") (name "Net-(U7-STAT)") (class "Default")
      (node (ref "TP17") (pin "1") (pinfunction "1_1") (pintype "passive"))
      (node (ref "U7") (pin "4") (pinfunction "STAT_4") (pintype "output"))
    )
    (net (code "50") (name "Net-(U8-CTL)") (class "Default")
      (node (ref "TP20") (pin "1") (pinfunction "1_1") (pintype "passive"))
      (node (ref "U8") (pin "3") (pinfunction "CTL_3") (pintype "input"))
    )
    (net (code "51") (name "Net-(U8-OUT)") (class "Default")
      (node (ref "U8") (pin "5") (pinfunction "OUT_5") (pintype "output"))
      (node (ref "U9") (pin "1") (pinfunction "IN_1") (pintype "input"))
    )
    (net (code "52") (name "Net-(U8-STAT)") (class "Default")
      (node (ref "TP19") (pin "1") (pinfunction "1_1") (pintype "passive"))
      (node (ref "U8") (pin "4") (pinfunction "STAT_4") (pintype "output"))
    )
    (net (code "53") (name "Net-(U9-CTL)") (class "Default")
      (node (ref "TP23") (pin "1") (pinfunction "1_1") (pintype "passive"))
      (node (ref "U9") (pin "3") (pinfunction "CTL_3") (pintype "input"))
    )
    (net (code "54") (name "Net-(U9-STAT)") (class "Default")
      (node (ref "TP18") (pin "1") (pinfunction "1_1") (pintype "passive"))
      (node (ref "U9") (pin "4") (pinfunction "STAT_4") (pintype "output"))
    )
    (net (code "55") (name "unconnected-(U6-PA1-Pad7)") (class "Default")
      (node (ref "U6") (pin "7") (pinfunction "PA1_7") (pintype "bidirectional"))
    )
    (net (code "56") (name "unconnected-(U6-PA8-Pad18)") (class "Default")
      (node (ref "U6") (pin "18") (pinfunction "PA8_18") (pintype "bidirectional"))
    )
    (net (code "57") (name "unconnected-(U6-PA15-Pad25)") (class "Default")
      (node (ref "U6") (pin "25") (pinfunction "PA15_25") (pintype "bidirectional"))
    )
    (net (code "58") (name "unconnected-(U6-PB0-Pad14)") (class "Default")
      (node (ref "U6") (pin "14") (pinfunction "PB0_14") (pintype "bidirectional"))
    )
    (net (code "59") (name "unconnected-(U6-PB1-Pad15)") (class "Default")
      (node (ref "U6") (pin "15") (pinfunction "PB1_15") (pintype "bidirectional"))
    )
    (net (code "60") (name "unconnected-(U6-PB5-Pad28)") (class "Default")
      (node (ref "U6") (pin "28") (pinfunction "PB5_28") (pintype "bidirectional"))
    )
  )
)
